# pth_supply.net
KiCad netlist of a schematic drawn in EAGLE
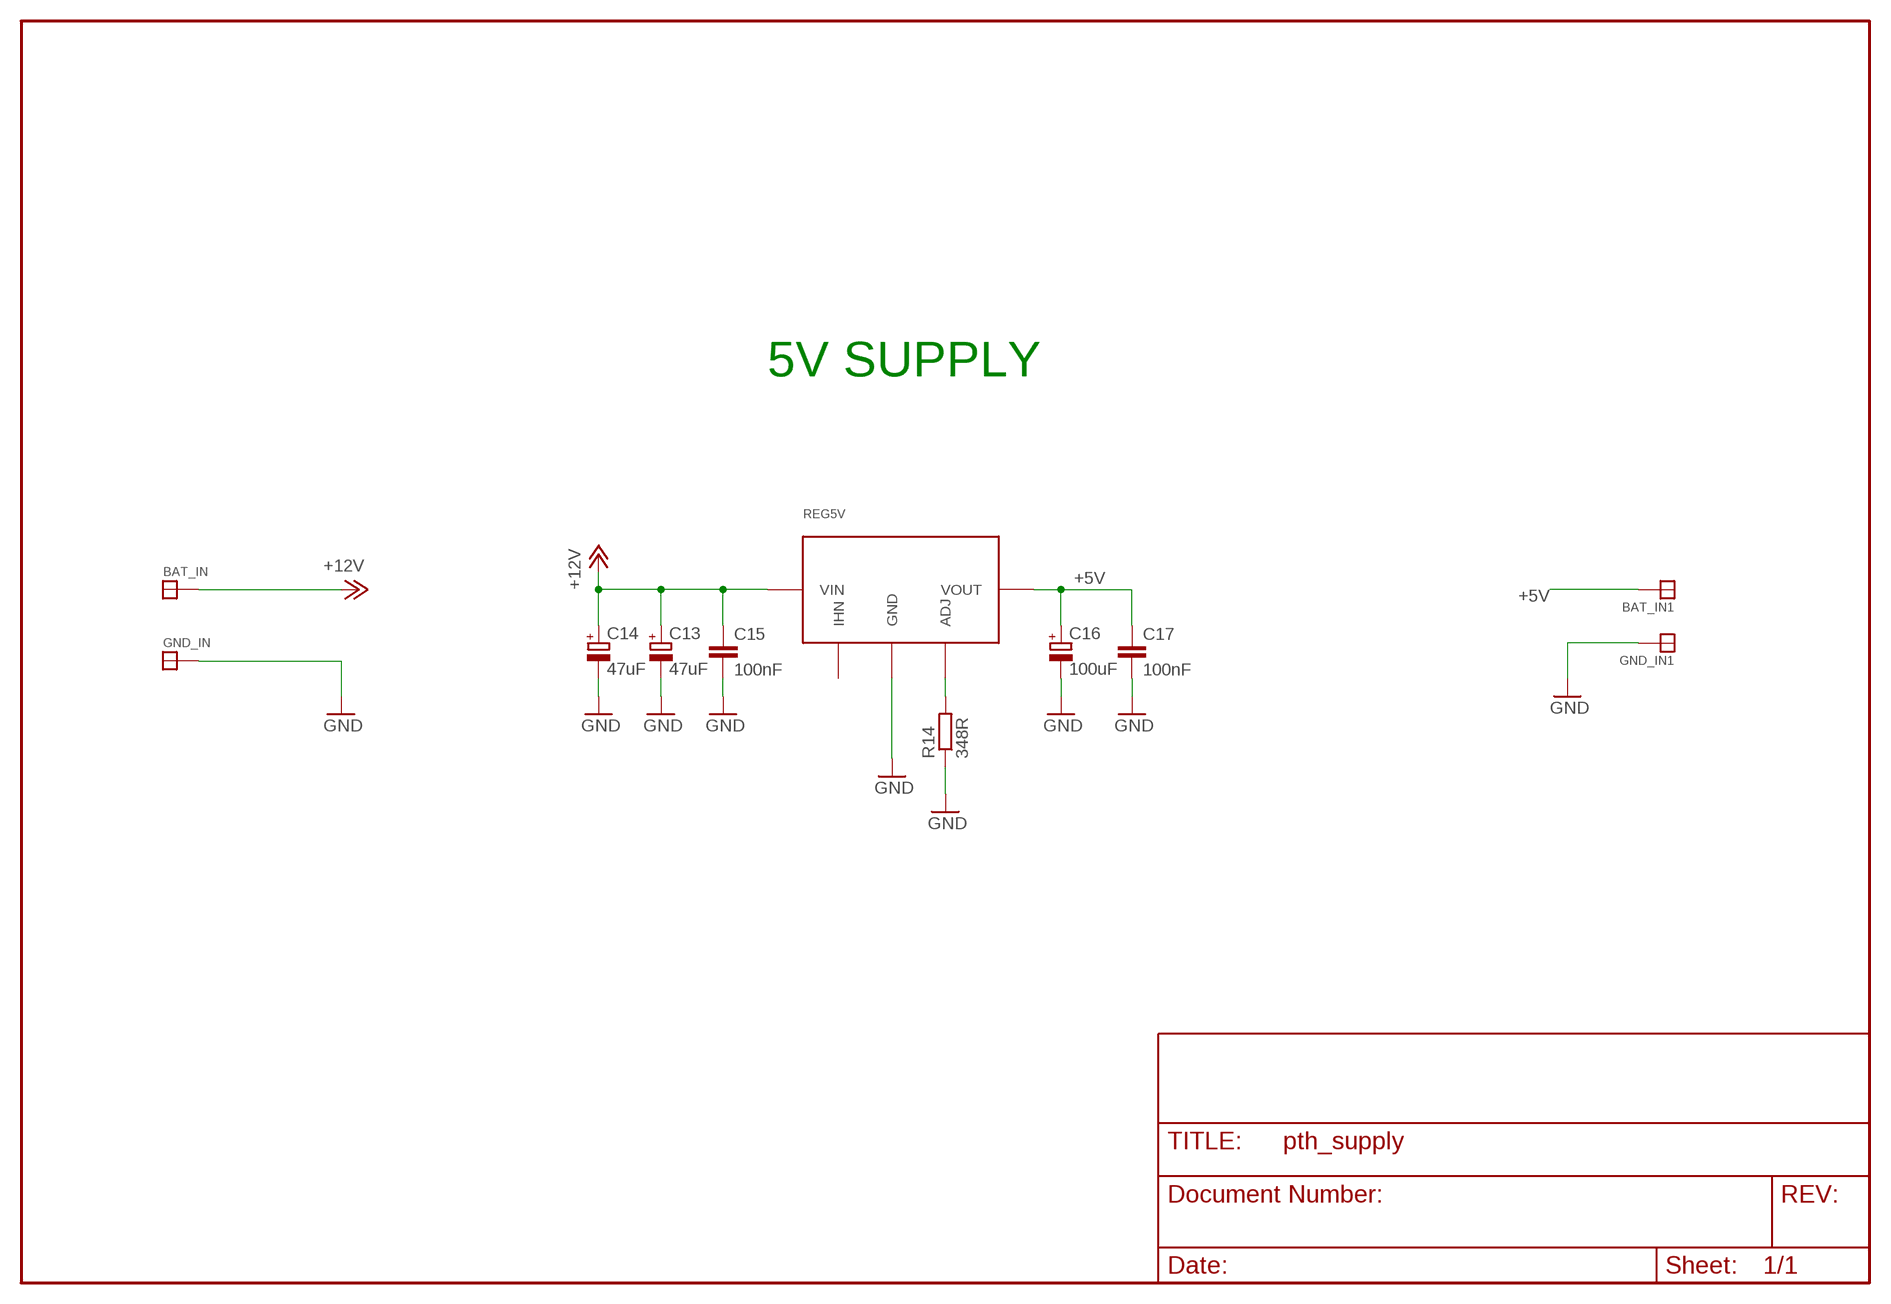
[diagram p0: schematic, sheet 1]

(export (version "E")
  (design (tool "Eeschema 10.0.6"))
  (components
    (comp (ref "BAT_IN")
      (value "SOLDER_PAD150_75")
      (footprint "eagle-import:SOLD_PAD_150_75")
      (libsource (lib "eagle-import") (part "SOLDER_PAD150_75"))
    )
    (comp (ref "BAT_IN1")
      (value "SOLDER_PAD150_75")
      (footprint "eagle-import:SOLD_PAD_150_75")
      (libsource (lib "eagle-import") (part "SOLDER_PAD150_75"))
    )
    (comp (ref "C13")
      (value "47uF")
      (footprint "eagle-import:SMC_D")
      (libsource (lib "eagle-import") (part "CPOL-EUSMCD"))
    )
    (comp (ref "C14")
      (value "47uF")
      (footprint "eagle-import:SMC_D")
      (libsource (lib "eagle-import") (part "CPOL-EUSMCD"))
    )
    (comp (ref "C15")
      (value "100nF")
      (footprint "eagle-import:C0805K")
      (libsource (lib "eagle-import") (part "C-EUC0805K"))
    )
    (comp (ref "C16")
      (value "100uF")
      (footprint "eagle-import:SMC_D")
      (libsource (lib "eagle-import") (part "CPOL-EUSMCD"))
    )
    (comp (ref "C17")
      (value "100nF")
      (footprint "eagle-import:C0805K")
      (libsource (lib "eagle-import") (part "C-EUC0805K"))
    )
    (comp (ref "GND_IN")
      (value "SOLDER_PAD150_75")
      (footprint "eagle-import:SOLD_PAD_150_75")
      (libsource (lib "eagle-import") (part "SOLDER_PAD150_75"))
    )
    (comp (ref "GND_IN1")
      (value "SOLDER_PAD150_75")
      (footprint "eagle-import:SOLD_PAD_150_75")
      (libsource (lib "eagle-import") (part "SOLDER_PAD150_75"))
    )
    (comp (ref "R14")
      (value "348R")
      (footprint "eagle-import:R1206")
      (libsource (lib "eagle-import") (part "R-EU_R1206"))
    )
    (comp (ref "REG5V")
      (value "PTH")
      (footprint "eagle-import:PTH")
      (libsource (lib "eagle-import") (part "PTH"))
    )
  )
  (nets
    (net (code "1") (name "+12V") (class "Default")
      (node (ref "BAT_IN") (pin "P$1") (pinfunction "P$1_P$1") (pintype "bidirectional"))
      (node (ref "C13") (pin "+") (pinfunction "+_+") (pintype "passive"))
      (node (ref "C14") (pin "+") (pinfunction "+_+") (pintype "passive"))
      (node (ref "C15") (pin "1") (pinfunction "1_1") (pintype "passive"))
      (node (ref "REG5V") (pin "P$1") (pinfunction "VIN_P$1") (pintype "bidirectional"))
    )
    (net (code "2") (name "/+5V") (class "Default")
      (node (ref "BAT_IN1") (pin "P$1") (pinfunction "P$1_P$1") (pintype "bidirectional"))
      (node (ref "C16") (pin "+") (pinfunction "+_+") (pintype "passive"))
      (node (ref "C17") (pin "1") (pinfunction "1_1") (pintype "passive"))
      (node (ref "REG5V") (pin "P$3") (pinfunction "VOUT_P$3") (pintype "bidirectional"))
    )
    (net (code "3") (name "GND") (class "Default")
      (node (ref "C13") (pin "-") (pinfunction "-_-") (pintype "passive"))
      (node (ref "C14") (pin "-") (pinfunction "-_-") (pintype "passive"))
      (node (ref "C15") (pin "2") (pinfunction "2_2") (pintype "passive"))
      (node (ref "C16") (pin "-") (pinfunction "-_-") (pintype "passive"))
      (node (ref "C17") (pin "2") (pinfunction "2_2") (pintype "passive"))
      (node (ref "GND_IN") (pin "P$1") (pinfunction "P$1_P$1") (pintype "bidirectional"))
      (node (ref "GND_IN1") (pin "P$1") (pinfunction "P$1_P$1") (pintype "bidirectional"))
      (node (ref "R14") (pin "1") (pinfunction "1_1") (pintype "passive"))
      (node (ref "REG5V") (pin "P$2") (pinfunction "GND_P$2") (pintype "bidirectional"))
    )
    (net (code "4") (name "Net-(REG5V-ADJ)") (class "Default")
      (node (ref "R14") (pin "2") (pinfunction "2_2") (pintype "passive"))
      (node (ref "REG5V") (pin "P$4") (pinfunction "ADJ_P$4") (pintype "bidirectional"))
    )
    (net (code "5") (name "unconnected-(REG5V-IHN-PadP$5)") (class "Default")
      (node (ref "REG5V") (pin "P$5") (pinfunction "IHN_P$5") (pintype "bidirectional"))
    )
  )
)
